# ReflectanceSensorBreakout_Alpha1a.net
KiCad netlist of a schematic drawn in EAGLE
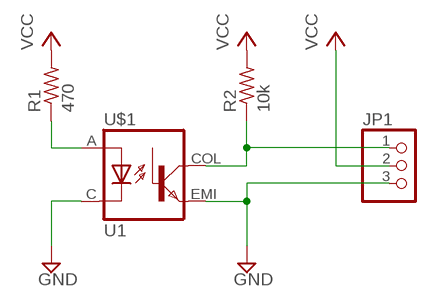
[diagram p0: schematic, sheet 1]

(export (version "E")
  (design (tool "Eeschema 10.0.6"))
  (components
    (comp (ref "JP1")
      (value "PINHD-1X3")
      (footprint "eagle-import:1X03")
      (libsource (lib "eagle-import") (part "PINHD-1X3"))
    )
    (comp (ref "R1")
      (value "470")
      (footprint "eagle-import:0204_7")
      (libsource (lib "eagle-import") (part "R-US_0204/7"))
    )
    (comp (ref "R2")
      (value "10k")
      (footprint "eagle-import:0204_7")
      (libsource (lib "eagle-import") (part "R-US_0204/7"))
    )
    (comp (ref "U$1")
      (value "U1")
      (footprint "eagle-import:ADAFRUIT_REFLECTANCE_SENSOR")
      (libsource (lib "eagle-import") (part "ADAFRUIT_REFLECTANCE_SENSOR"))
    )
  )
  (nets
    (net (code "1") (name "GND") (class "Default")
      (node (ref "JP1") (pin "3") (pinfunction "3_3") (pintype "passive"))
      (node (ref "U$1") (pin "C") (pinfunction "C_C") (pintype "passive"))
      (node (ref "U$1") (pin "EMI") (pinfunction "EMI_EMI") (pintype "passive"))
    )
    (net (code "2") (name "Net-(JP1-Pad1)") (class "Default")
      (node (ref "JP1") (pin "1") (pinfunction "1_1") (pintype "passive"))
      (node (ref "R2") (pin "1") (pinfunction "1_1") (pintype "passive"))
      (node (ref "U$1") (pin "COL") (pinfunction "COL_COL") (pintype "passive"))
    )
    (net (code "3") (name "Net-(R1-Pad1)") (class "Default")
      (node (ref "R1") (pin "1") (pinfunction "1_1") (pintype "passive"))
      (node (ref "U$1") (pin "A") (pinfunction "A_A") (pintype "passive"))
    )
    (net (code "4") (name "VCC") (class "Default")
      (node (ref "JP1") (pin "2") (pinfunction "2_2") (pintype "passive"))
      (node (ref "R1") (pin "2") (pinfunction "2_2") (pintype "passive"))
      (node (ref "R2") (pin "2") (pinfunction "2_2") (pintype "passive"))
    )
  )
)
